# cap_sensor.net
KiCad netlist of a schematic drawn in EAGLE
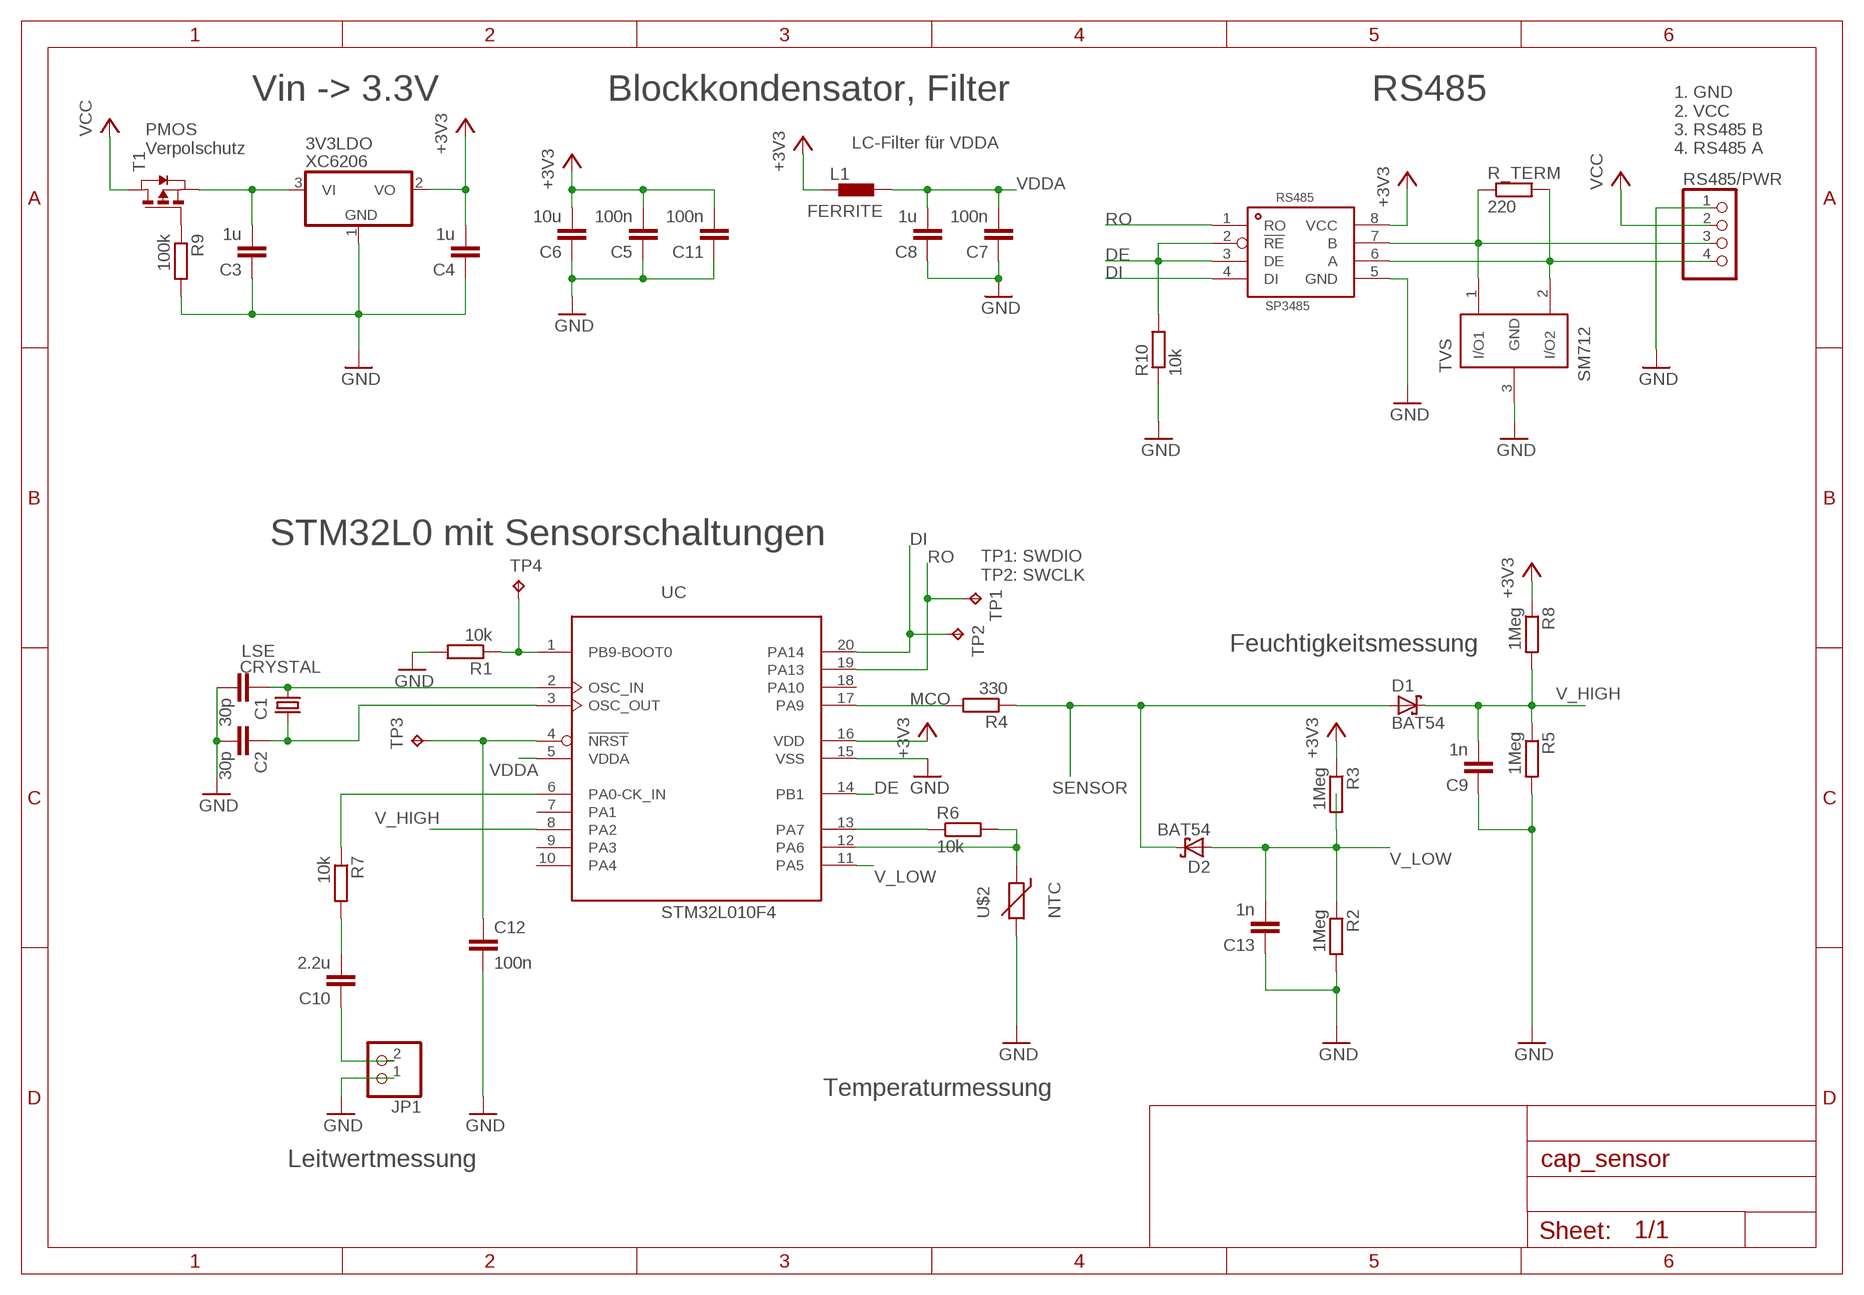
[diagram p0: schematic, sheet 1]

(export (version "E")
  (design (tool "Eeschema 10.0.6"))
  (components
    (comp (ref "3V3LDO")
      (value "XC6206")
      (footprint "eagle-import:SOT23-3")
      (libsource (lib "eagle-import") (part "XC6206"))
    )
    (comp (ref "C1")
      (value "30p")
      (footprint "eagle-import:C0603")
      (libsource (lib "eagle-import") (part "C-EUC0603"))
    )
    (comp (ref "C2")
      (value "30p")
      (footprint "eagle-import:C0603")
      (libsource (lib "eagle-import") (part "C-EUC0603"))
    )
    (comp (ref "C3")
      (value "1u")
      (footprint "eagle-import:C0603")
      (libsource (lib "eagle-import") (part "C-EUC0603"))
    )
    (comp (ref "C4")
      (value "1u")
      (footprint "eagle-import:C0603")
      (libsource (lib "eagle-import") (part "C-EUC0603"))
    )
    (comp (ref "C5")
      (value "100n")
      (footprint "eagle-import:C0603")
      (libsource (lib "eagle-import") (part "C-EUC0603"))
    )
    (comp (ref "C6")
      (value "10u")
      (footprint "eagle-import:C0603")
      (libsource (lib "eagle-import") (part "C-EUC0603"))
    )
    (comp (ref "C7")
      (value "100n")
      (footprint "eagle-import:C0603")
      (libsource (lib "eagle-import") (part "C-EUC0603"))
    )
    (comp (ref "C8")
      (value "1u")
      (footprint "eagle-import:C0603")
      (libsource (lib "eagle-import") (part "C-EUC0603"))
    )
    (comp (ref "C9")
      (value "1n")
      (footprint "eagle-import:C0603")
      (libsource (lib "eagle-import") (part "C-EUC0603"))
    )
    (comp (ref "C10")
      (value "2.2u")
      (footprint "eagle-import:C0603")
      (libsource (lib "eagle-import") (part "C-EUC0603"))
    )
    (comp (ref "C11")
      (value "100n")
      (footprint "eagle-import:C0603")
      (libsource (lib "eagle-import") (part "C-EUC0603"))
    )
    (comp (ref "C12")
      (value "100n")
      (footprint "eagle-import:C0603")
      (libsource (lib "eagle-import") (part "C-EUC0603"))
    )
    (comp (ref "C13")
      (value "1n")
      (footprint "eagle-import:C0603")
      (libsource (lib "eagle-import") (part "C-EUC0603"))
    )
    (comp (ref "D1")
      (value "BAT54")
      (footprint "eagle-import:SOT23")
      (libsource (lib "eagle-import") (part "BAT54"))
    )
    (comp (ref "D2")
      (value "BAT54")
      (footprint "eagle-import:SOT23")
      (libsource (lib "eagle-import") (part "BAT54"))
    )
    (comp (ref "JP1")
      (value "PINHD-1X2")
      (footprint "eagle-import:1X02")
      (libsource (lib "eagle-import") (part "PINHD-1X2"))
    )
    (comp (ref "L1")
      (value "FERRITE")
      (footprint "eagle-import:R0603")
      (libsource (lib "eagle-import") (part "FERRITE"))
    )
    (comp (ref "LSE")
      (value "CRYSTAL")
      (footprint "eagle-import:CRYSTAL-3.2X1.5")
      (libsource (lib "eagle-import") (part "CRYSTAL"))
    )
    (comp (ref "R1")
      (value "10k")
      (footprint "eagle-import:R0603")
      (libsource (lib "eagle-import") (part "R-EU_R0603"))
    )
    (comp (ref "R2")
      (value "1Meg")
      (footprint "eagle-import:R0603")
      (libsource (lib "eagle-import") (part "R-EU_R0603"))
    )
    (comp (ref "R3")
      (value "1Meg")
      (footprint "eagle-import:R0603")
      (libsource (lib "eagle-import") (part "R-EU_R0603"))
    )
    (comp (ref "R4")
      (value "330")
      (footprint "eagle-import:R0603")
      (libsource (lib "eagle-import") (part "R-EU_R0603"))
    )
    (comp (ref "R5")
      (value "1Meg")
      (footprint "eagle-import:R0603")
      (libsource (lib "eagle-import") (part "R-EU_R0603"))
    )
    (comp (ref "R6")
      (value "10k")
      (footprint "eagle-import:R0603")
      (libsource (lib "eagle-import") (part "R-EU_R0603"))
    )
    (comp (ref "R7")
      (value "10k")
      (footprint "eagle-import:R0603")
      (libsource (lib "eagle-import") (part "R-EU_R0603"))
    )
    (comp (ref "R8")
      (value "1Meg")
      (footprint "eagle-import:R0603")
      (libsource (lib "eagle-import") (part "R-EU_R0603"))
    )
    (comp (ref "R9")
      (value "100k")
      (footprint "eagle-import:R0603")
      (libsource (lib "eagle-import") (part "R-EU_R0603"))
    )
    (comp (ref "R10")
      (value "10k")
      (footprint "eagle-import:R0603")
      (libsource (lib "eagle-import") (part "R-EU_R0603"))
    )
    (comp (ref "RS485")
      (value "SP3485")
      (footprint "eagle-import:NSOIC8")
      (libsource (lib "eagle-import") (part "SP3485"))
    )
    (comp (ref "RS485/PWR")
      (value "PINHD-1X4")
      (footprint "eagle-import:1X04")
      (libsource (lib "eagle-import") (part "PINHD-1X4"))
    )
    (comp (ref "R_TERM")
      (value "220")
      (footprint "eagle-import:R0603")
      (libsource (lib "eagle-import") (part "R-EU_R0603"))
    )
    (comp (ref "T1")
      (value "PMOSSOT23")
      (footprint "eagle-import:SOT-23")
      (libsource (lib "eagle-import") (part "PMOSSOT23"))
    )
    (comp (ref "TP1")
      (value "TPTP12R")
      (footprint "eagle-import:TP12R")
      (libsource (lib "eagle-import") (part "TPTP12R"))
    )
    (comp (ref "TP2")
      (value "TPTP12R")
      (footprint "eagle-import:TP12R")
      (libsource (lib "eagle-import") (part "TPTP12R"))
    )
    (comp (ref "TP3")
      (value "TPTP12R")
      (footprint "eagle-import:TP12R")
      (libsource (lib "eagle-import") (part "TPTP12R"))
    )
    (comp (ref "TP4")
      (value "TPTP12R")
      (footprint "eagle-import:TP12R")
      (libsource (lib "eagle-import") (part "TPTP12R"))
    )
    (comp (ref "TVS")
      (value "SM712")
      (footprint "eagle-import:SOT23-3")
      (libsource (lib "eagle-import") (part "SM712"))
    )
    (comp (ref "U$2")
      (value "NTC")
      (footprint "eagle-import:R0603")
      (libsource (lib "eagle-import") (part "NTC"))
    )
    (comp (ref "UC")
      (value "STM32L010F4")
      (footprint "eagle-import:TSSOP20-I")
      (libsource (lib "eagle-import") (part "STM32L010F4"))
    )
  )
  (nets
    (net (code "1") (name "+3V3") (class "Default")
      (node (ref "3V3LDO") (pin "2") (pinfunction "VO_2") (pintype "power_in"))
      (node (ref "C11") (pin "2") (pinfunction "2_2") (pintype "passive"))
      (node (ref "C4") (pin "2") (pinfunction "2_2") (pintype "passive"))
      (node (ref "C5") (pin "2") (pinfunction "2_2") (pintype "passive"))
      (node (ref "C6") (pin "2") (pinfunction "2_2") (pintype "passive"))
      (node (ref "L1") (pin "1") (pinfunction "1_1") (pintype "passive"))
      (node (ref "R3") (pin "1") (pinfunction "1_1") (pintype "passive"))
      (node (ref "R8") (pin "1") (pinfunction "1_1") (pintype "passive"))
      (node (ref "RS485") (pin "8") (pinfunction "VCC_8") (pintype "power_in"))
      (node (ref "UC") (pin "16") (pinfunction "VDD_16") (pintype "power_in"))
    )
    (net (code "2") (name "/DE") (class "Default")
      (node (ref "R10") (pin "2") (pinfunction "2_2") (pintype "passive"))
      (node (ref "RS485") (pin "2") (pinfunction "~{RE}_2") (pintype "bidirectional"))
      (node (ref "RS485") (pin "3") (pinfunction "DE_3") (pintype "bidirectional"))
      (node (ref "UC") (pin "14") (pinfunction "PB1_14") (pintype "bidirectional"))
    )
    (net (code "3") (name "/DI") (class "Default")
      (node (ref "RS485") (pin "4") (pinfunction "DI_4") (pintype "bidirectional"))
      (node (ref "TP2") (pin "TP") (pinfunction "TP_TP") (pintype "input"))
      (node (ref "UC") (pin "20") (pinfunction "PA14_20") (pintype "bidirectional"))
    )
    (net (code "4") (name "/MCO") (class "Default")
      (node (ref "R4") (pin "2") (pinfunction "2_2") (pintype "passive"))
      (node (ref "UC") (pin "17") (pinfunction "PA9_17") (pintype "bidirectional"))
    )
    (net (code "5") (name "/RO") (class "Default")
      (node (ref "RS485") (pin "1") (pinfunction "RO_1") (pintype "bidirectional"))
      (node (ref "TP1") (pin "TP") (pinfunction "TP_TP") (pintype "input"))
      (node (ref "UC") (pin "19") (pinfunction "PA13_19") (pintype "bidirectional"))
    )
    (net (code "6") (name "/SENSOR") (class "Default")
      (node (ref "D1") (pin "1") (pinfunction "A_1") (pintype "passive"))
      (node (ref "D2") (pin "3") (pinfunction "C_3") (pintype "passive"))
      (node (ref "R4") (pin "1") (pinfunction "1_1") (pintype "passive"))
    )
    (net (code "7") (name "/VDDA") (class "Default")
      (node (ref "C7") (pin "2") (pinfunction "2_2") (pintype "passive"))
      (node (ref "C8") (pin "2") (pinfunction "2_2") (pintype "passive"))
      (node (ref "L1") (pin "2") (pinfunction "2_2") (pintype "passive"))
      (node (ref "UC") (pin "5") (pinfunction "VDDA_5") (pintype "power_in"))
    )
    (net (code "8") (name "/V_HIGH") (class "Default")
      (node (ref "C9") (pin "2") (pinfunction "2_2") (pintype "passive"))
      (node (ref "D1") (pin "3") (pinfunction "C_3") (pintype "passive"))
      (node (ref "R5") (pin "1") (pinfunction "1_1") (pintype "passive"))
      (node (ref "R8") (pin "2") (pinfunction "2_2") (pintype "passive"))
      (node (ref "UC") (pin "8") (pinfunction "PA2_8") (pintype "bidirectional"))
    )
    (net (code "9") (name "/V_LOW") (class "Default")
      (node (ref "C13") (pin "2") (pinfunction "2_2") (pintype "passive"))
      (node (ref "D2") (pin "1") (pinfunction "A_1") (pintype "passive"))
      (node (ref "R2") (pin "1") (pinfunction "1_1") (pintype "passive"))
      (node (ref "R3") (pin "2") (pinfunction "2_2") (pintype "passive"))
      (node (ref "UC") (pin "11") (pinfunction "PA5_11") (pintype "bidirectional"))
    )
    (net (code "10") (name "GND") (class "Default")
      (node (ref "3V3LDO") (pin "1") (pinfunction "GND_1") (pintype "power_in"))
      (node (ref "C1") (pin "2") (pinfunction "2_2") (pintype "passive"))
      (node (ref "C11") (pin "1") (pinfunction "1_1") (pintype "passive"))
      (node (ref "C12") (pin "2") (pinfunction "2_2") (pintype "passive"))
      (node (ref "C13") (pin "1") (pinfunction "1_1") (pintype "passive"))
      (node (ref "C2") (pin "2") (pinfunction "2_2") (pintype "passive"))
      (node (ref "C3") (pin "1") (pinfunction "1_1") (pintype "passive"))
      (node (ref "C4") (pin "1") (pinfunction "1_1") (pintype "passive"))
      (node (ref "C5") (pin "1") (pinfunction "1_1") (pintype "passive"))
      (node (ref "C6") (pin "1") (pinfunction "1_1") (pintype "passive"))
      (node (ref "C7") (pin "1") (pinfunction "1_1") (pintype "passive"))
      (node (ref "C8") (pin "1") (pinfunction "1_1") (pintype "passive"))
      (node (ref "C9") (pin "1") (pinfunction "1_1") (pintype "passive"))
      (node (ref "JP1") (pin "1") (pinfunction "1_1") (pintype "passive"))
      (node (ref "R1") (pin "2") (pinfunction "2_2") (pintype "passive"))
      (node (ref "R10") (pin "1") (pinfunction "1_1") (pintype "passive"))
      (node (ref "R2") (pin "2") (pinfunction "2_2") (pintype "passive"))
      (node (ref "R5") (pin "2") (pinfunction "2_2") (pintype "passive"))
      (node (ref "R9") (pin "2") (pinfunction "2_2") (pintype "passive"))
      (node (ref "RS485") (pin "5") (pinfunction "GND_5") (pintype "power_in"))
      (node (ref "RS485/PWR") (pin "1") (pinfunction "1_1") (pintype "passive"))
      (node (ref "TVS") (pin "3") (pinfunction "GND_3") (pintype "power_in"))
      (node (ref "U$2") (pin "2") (pinfunction "2_2") (pintype "passive"))
      (node (ref "UC") (pin "15") (pinfunction "VSS_15") (pintype "power_in"))
    )
    (net (code "11") (name "Net-(3V3LDO-VI)") (class "Default")
      (node (ref "3V3LDO") (pin "3") (pinfunction "VI_3") (pintype "input"))
      (node (ref "C3") (pin "2") (pinfunction "2_2") (pintype "passive"))
      (node (ref "T1") (pin "2") (pinfunction "S_2") (pintype "passive"))
    )
    (net (code "12") (name "Net-(C10-Pad1)") (class "Default")
      (node (ref "C10") (pin "1") (pinfunction "1_1") (pintype "passive"))
      (node (ref "JP1") (pin "2") (pinfunction "2_2") (pintype "passive"))
    )
    (net (code "13") (name "Net-(C10-Pad2)") (class "Default")
      (node (ref "C10") (pin "2") (pinfunction "2_2") (pintype "passive"))
      (node (ref "R7") (pin "2") (pinfunction "2_2") (pintype "passive"))
    )
    (net (code "14") (name "Net-(RS485-A)") (class "Default")
      (node (ref "RS485") (pin "6") (pinfunction "A_6") (pintype "bidirectional"))
      (node (ref "RS485/PWR") (pin "4") (pinfunction "4_4") (pintype "passive"))
      (node (ref "R_TERM") (pin "2") (pinfunction "2_2") (pintype "passive"))
      (node (ref "TVS") (pin "2") (pinfunction "I/O2_2") (pintype "bidirectional"))
    )
    (net (code "15") (name "Net-(RS485-B)") (class "Default")
      (node (ref "RS485") (pin "7") (pinfunction "B_7") (pintype "bidirectional"))
      (node (ref "RS485/PWR") (pin "3") (pinfunction "3_3") (pintype "passive"))
      (node (ref "R_TERM") (pin "1") (pinfunction "1_1") (pintype "passive"))
      (node (ref "TVS") (pin "1") (pinfunction "I/O1_1") (pintype "bidirectional"))
    )
    (net (code "16") (name "Net-(T1-G)") (class "Default")
      (node (ref "R9") (pin "1") (pinfunction "1_1") (pintype "passive"))
      (node (ref "T1") (pin "3") (pinfunction "G_3") (pintype "passive"))
    )
    (net (code "17") (name "Net-(UC-OSC_IN)") (class "Default")
      (node (ref "C1") (pin "1") (pinfunction "1_1") (pintype "passive"))
      (node (ref "LSE") (pin "1") (pinfunction "1_1") (pintype "passive"))
      (node (ref "UC") (pin "2") (pinfunction "OSC_IN_2") (pintype "bidirectional"))
    )
    (net (code "18") (name "Net-(UC-OSC_OUT)") (class "Default")
      (node (ref "C2") (pin "1") (pinfunction "1_1") (pintype "passive"))
      (node (ref "LSE") (pin "2") (pinfunction "2_2") (pintype "passive"))
      (node (ref "UC") (pin "3") (pinfunction "OSC_OUT_3") (pintype "bidirectional"))
    )
    (net (code "19") (name "Net-(UC-PA0-CK_IN)") (class "Default")
      (node (ref "R7") (pin "1") (pinfunction "1_1") (pintype "passive"))
      (node (ref "UC") (pin "6") (pinfunction "PA0-CK_IN_6") (pintype "bidirectional"))
    )
    (net (code "20") (name "Net-(UC-PA6)") (class "Default")
      (node (ref "R6") (pin "2") (pinfunction "2_2") (pintype "passive"))
      (node (ref "U$2") (pin "1") (pinfunction "1_1") (pintype "passive"))
      (node (ref "UC") (pin "12") (pinfunction "PA6_12") (pintype "bidirectional"))
    )
    (net (code "21") (name "Net-(UC-PA7)") (class "Default")
      (node (ref "R6") (pin "1") (pinfunction "1_1") (pintype "passive"))
      (node (ref "UC") (pin "13") (pinfunction "PA7_13") (pintype "bidirectional"))
    )
    (net (code "22") (name "Net-(UC-PB9-BOOT0)") (class "Default")
      (node (ref "R1") (pin "1") (pinfunction "1_1") (pintype "passive"))
      (node (ref "TP4") (pin "TP") (pinfunction "TP_TP") (pintype "input"))
      (node (ref "UC") (pin "1") (pinfunction "PB9-BOOT0_1") (pintype "input"))
    )
    (net (code "23") (name "Net-(UC-~{NRST})") (class "Default")
      (node (ref "C12") (pin "1") (pinfunction "1_1") (pintype "passive"))
      (node (ref "TP3") (pin "TP") (pinfunction "TP_TP") (pintype "input"))
      (node (ref "UC") (pin "4") (pinfunction "~{NRST}_4") (pintype "bidirectional"))
    )
    (net (code "24") (name "VCC") (class "Default")
      (node (ref "RS485/PWR") (pin "2") (pinfunction "2_2") (pintype "passive"))
      (node (ref "T1") (pin "1") (pinfunction "D_1") (pintype "passive"))
    )
    (net (code "25") (name "unconnected-(UC-PA1-Pad7)") (class "Default")
      (node (ref "UC") (pin "7") (pinfunction "PA1_7") (pintype "bidirectional"))
    )
    (net (code "26") (name "unconnected-(UC-PA3-Pad9)") (class "Default")
      (node (ref "UC") (pin "9") (pinfunction "PA3_9") (pintype "bidirectional"))
    )
    (net (code "27") (name "unconnected-(UC-PA4-Pad10)") (class "Default")
      (node (ref "UC") (pin "10") (pinfunction "PA4_10") (pintype "bidirectional"))
    )
    (net (code "28") (name "unconnected-(UC-PA10-Pad18)") (class "Default")
      (node (ref "UC") (pin "18") (pinfunction "PA10_18") (pintype "bidirectional"))
    )
  )
)
